# IntegratedSensor.net
KiCad netlist of a schematic drawn in EAGLE
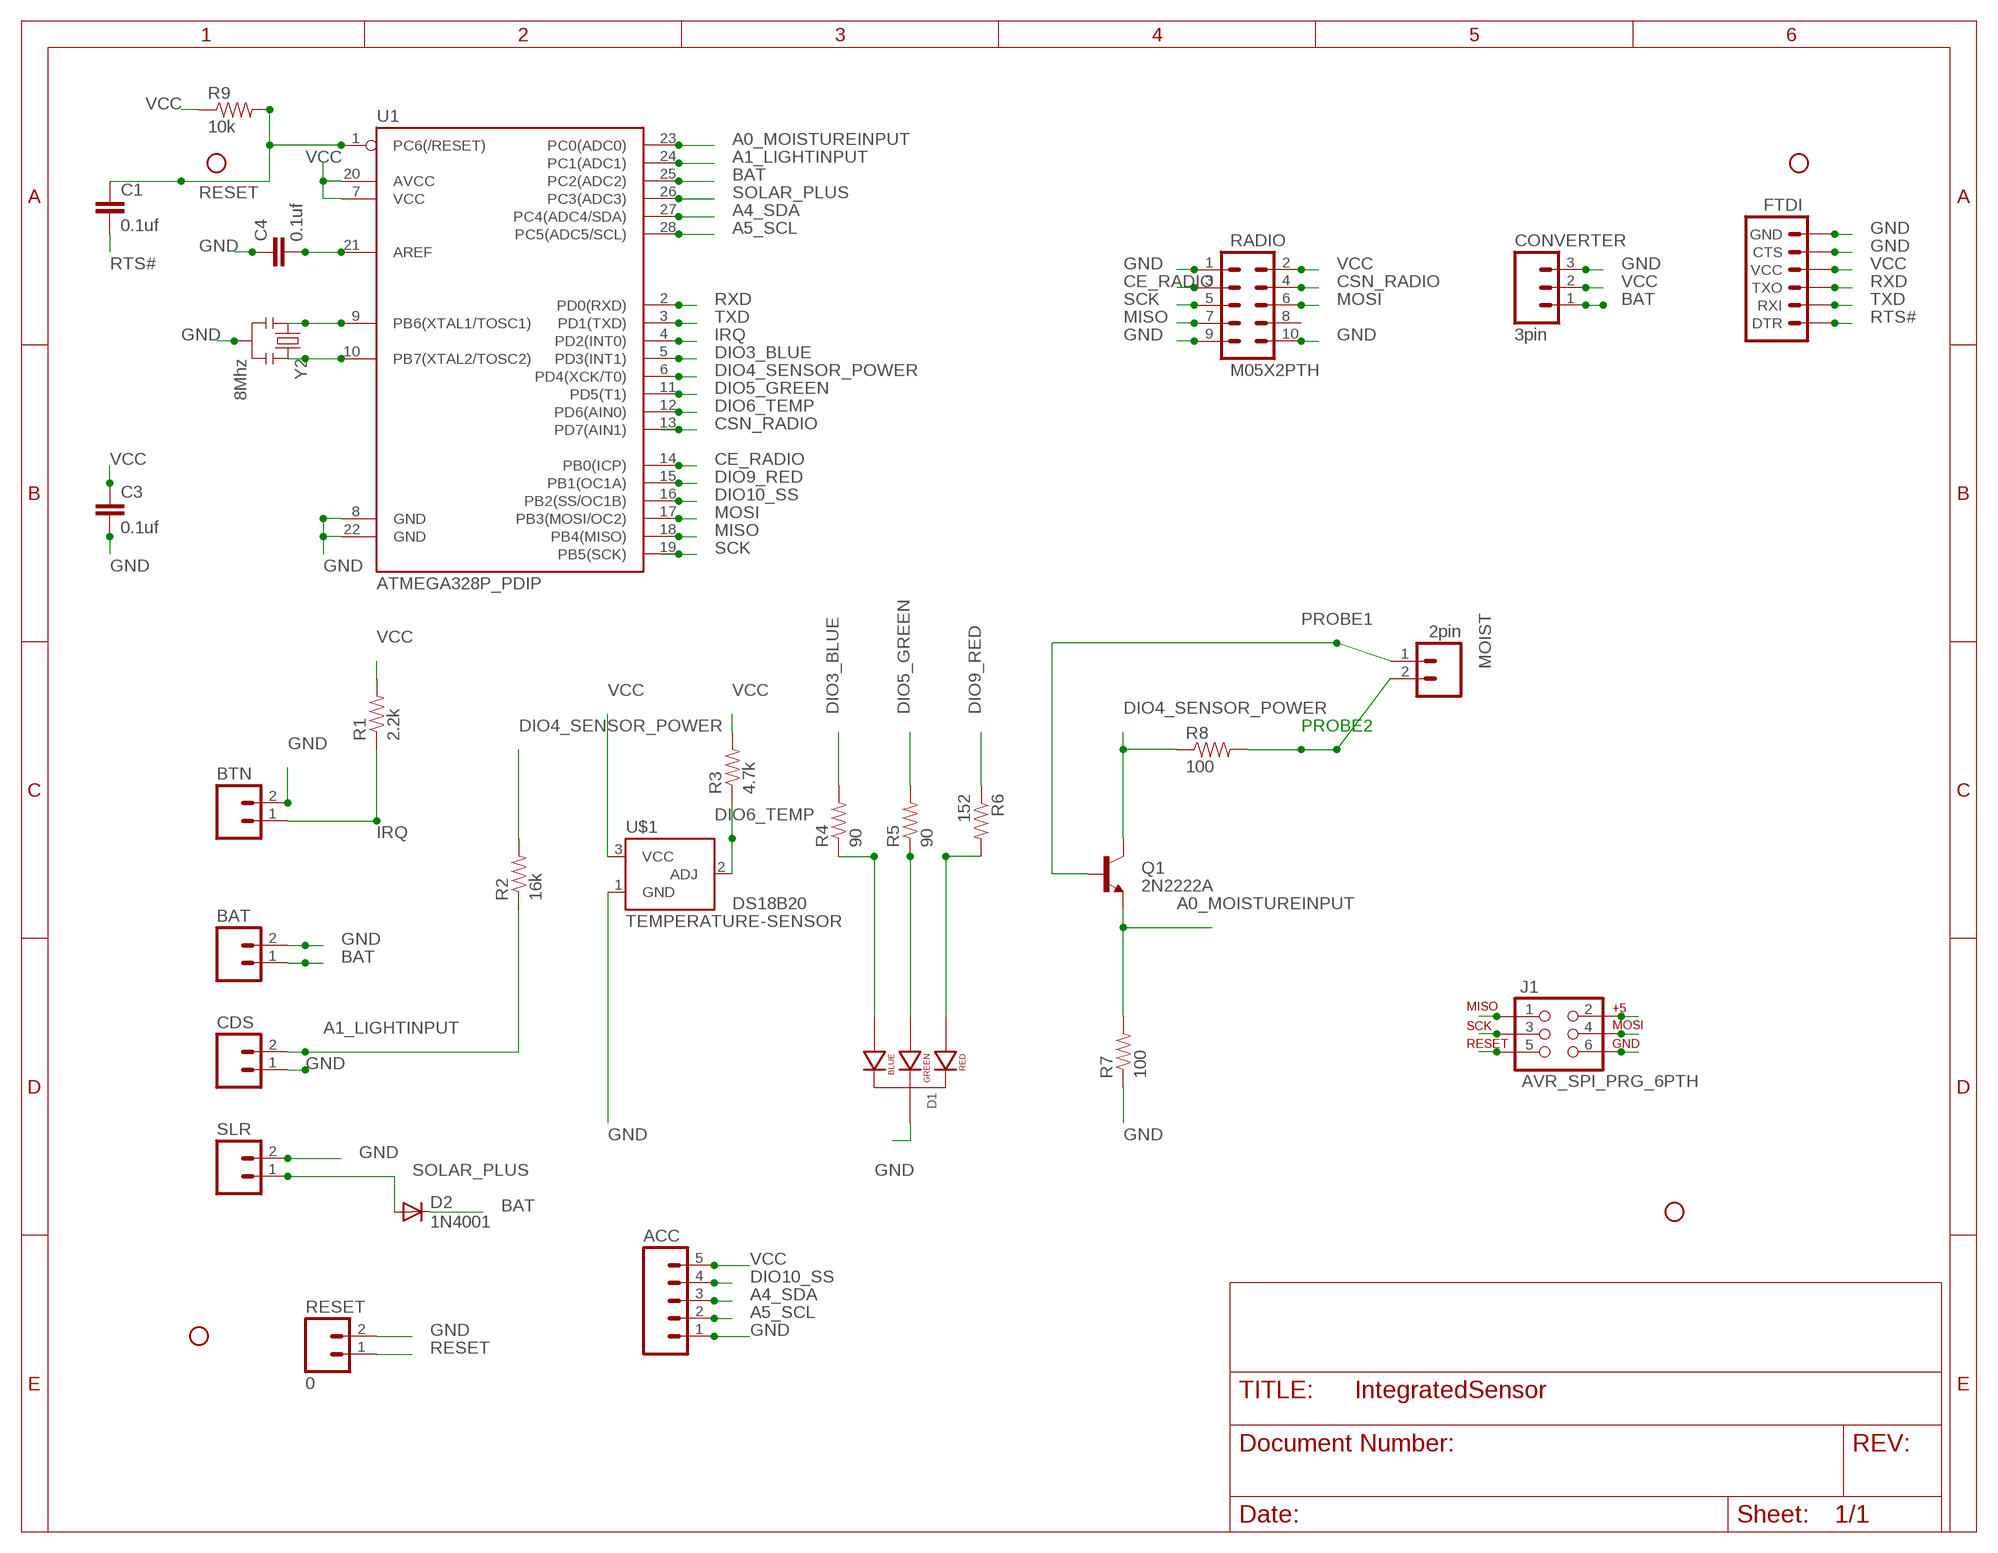
[diagram p0: schematic, sheet 1]

(export (version "E")
  (design (tool "Eeschema 10.0.6"))
  (components
    (comp (ref "ACC")
      (value "M05PTH")
      (footprint "eagle-import:1X05")
      (libsource (lib "eagle-import") (part "M05PTH"))
    )
    (comp (ref "BAT")
      (value "M02PTH")
      (footprint "eagle-import:1X02")
      (libsource (lib "eagle-import") (part "M02PTH"))
    )
    (comp (ref "BTN")
      (value "M02PTH")
      (footprint "eagle-import:1X02")
      (libsource (lib "eagle-import") (part "M02PTH"))
    )
    (comp (ref "C1")
      (value "0.1uf")
      (footprint "eagle-import:CAP-PTH-SMALL")
      (libsource (lib "eagle-import") (part "CAPPTH"))
    )
    (comp (ref "C3")
      (value "0.1uf")
      (footprint "eagle-import:CAP-PTH-SMALL")
      (libsource (lib "eagle-import") (part "CAPPTH"))
    )
    (comp (ref "C4")
      (value "0.1uf")
      (footprint "eagle-import:CAP-PTH-SMALL")
      (libsource (lib "eagle-import") (part "CAPPTH"))
    )
    (comp (ref "CDS")
      (value "M02PTH")
      (footprint "eagle-import:1X02")
      (libsource (lib "eagle-import") (part "M02PTH"))
    )
    (comp (ref "CONVERTER")
      (value "3pin")
      (footprint "eagle-import:1X03")
      (libsource (lib "eagle-import") (part "M03PTH"))
    )
    (comp (ref "D1")
      (value "LED-RGB-CC-THRUCLEAR")
      (footprint "eagle-import:LED-RGB-THRU")
      (libsource (lib "eagle-import") (part "LED-RGB-CC-THRUCLEAR"))
    )
    (comp (ref "D2")
      (value "1N4001")
      (footprint "eagle-import:DIODE-1N4001")
      (libsource (lib "eagle-import") (part "DIODEPTH"))
    )
    (comp (ref "FTDI")
      (value "ARDUINO_SERIAL_PROGRAMPTH")
      (footprint "eagle-import:1X06")
      (libsource (lib "eagle-import") (part "ARDUINO_SERIAL_PROGRAMPTH"))
    )
    (comp (ref "J1")
      (value "AVR_SPI_PRG_6PTH")
      (footprint "eagle-import:2X3")
      (libsource (lib "eagle-import") (part "AVR_SPI_PRG_6PTH"))
    )
    (comp (ref "MOIST")
      (value "2pin")
      (footprint "eagle-import:1X02")
      (libsource (lib "eagle-import") (part "M02PTH"))
    )
    (comp (ref "Q1")
      (value "2N2222A")
      (footprint "eagle-import:TO-92-AMMO")
      (libsource (lib "eagle-import") (part "TRANSISTOR_NPNTO-92-AMMO"))
    )
    (comp (ref "R1")
      (value "2.2k")
      (footprint "eagle-import:1_6W-RES")
      (libsource (lib "eagle-import") (part "RESISTORPTH-1/6W"))
    )
    (comp (ref "R2")
      (value "16k")
      (footprint "eagle-import:1_6W-RES")
      (libsource (lib "eagle-import") (part "RESISTORPTH-1/6W"))
    )
    (comp (ref "R3")
      (value "4.7k")
      (footprint "eagle-import:1_6W-RES")
      (libsource (lib "eagle-import") (part "RESISTORPTH-1/6W"))
    )
    (comp (ref "R4")
      (value "90")
      (footprint "eagle-import:1_6W-RES")
      (libsource (lib "eagle-import") (part "RESISTORPTH-1/6W"))
    )
    (comp (ref "R5")
      (value "90")
      (footprint "eagle-import:1_6W-RES")
      (libsource (lib "eagle-import") (part "RESISTORPTH-1/6W"))
    )
    (comp (ref "R6")
      (value "152")
      (footprint "eagle-import:1_6W-RES")
      (libsource (lib "eagle-import") (part "RESISTORPTH-1/6W"))
    )
    (comp (ref "R7")
      (value "100")
      (footprint "eagle-import:1_6W-RES")
      (libsource (lib "eagle-import") (part "RESISTORPTH-1/6W"))
    )
    (comp (ref "R8")
      (value "100")
      (footprint "eagle-import:1_6W-RES")
      (libsource (lib "eagle-import") (part "RESISTORPTH-1/6W"))
    )
    (comp (ref "R9")
      (value "10k")
      (footprint "eagle-import:1_6W-RES")
      (libsource (lib "eagle-import") (part "RESISTORPTH-1/6W"))
    )
    (comp (ref "RADIO")
      (value "M05X2PTH")
      (footprint "eagle-import:AVR_ICSP")
      (libsource (lib "eagle-import") (part "M05X2PTH"))
    )
    (comp (ref "RESET")
      (value "0")
      (footprint "eagle-import:1X02")
      (libsource (lib "eagle-import") (part "M02PTH"))
    )
    (comp (ref "SLR")
      (value "M02PTH")
      (footprint "eagle-import:1X02")
      (libsource (lib "eagle-import") (part "M02PTH"))
    )
    (comp (ref "STANDOFF1")
      (value "STAND-OFF")
      (footprint "eagle-import:STAND-OFF")
      (libsource (lib "eagle-import") (part "STAND-OFF"))
    )
    (comp (ref "STANDOFF2")
      (value "STAND-OFF")
      (footprint "eagle-import:STAND-OFF")
      (libsource (lib "eagle-import") (part "STAND-OFF"))
    )
    (comp (ref "STANDOFF3")
      (value "STAND-OFF")
      (footprint "eagle-import:STAND-OFF")
      (libsource (lib "eagle-import") (part "STAND-OFF"))
    )
    (comp (ref "STANDOFF4")
      (value "STAND-OFF")
      (footprint "eagle-import:STAND-OFF")
      (libsource (lib "eagle-import") (part "STAND-OFF"))
    )
    (comp (ref "U$1")
      (value "TEMPERATURE-SENSOR")
      (footprint "eagle-import:TO-92")
      (fields (field (name "PARTNAME") "DS18B20"))
      (libsource (lib "eagle-import") (part "TEMPERATURE-SENSOR"))
    )
    (comp (ref "U1")
      (value "ATMEGA328P_PDIP")
      (footprint "eagle-import:DIL28-3")
      (libsource (lib "eagle-import") (part "ATMEGA328P_PDIP"))
    )
    (comp (ref "Y2")
      (value "8Mhz")
      (footprint "eagle-import:RESONATOR-PTH")
      (libsource (lib "eagle-import") (part "RESONATORPTH"))
    )
  )
  (nets
    (net (code "1") (name "/A0_MOISTUREINPUT") (class "Default")
      (node (ref "Q1") (pin "1") (pinfunction "E_1") (pintype "passive"))
      (node (ref "R7") (pin "2") (pinfunction "2_2") (pintype "passive"))
      (node (ref "U1") (pin "23") (pinfunction "PC0(ADC0)_23") (pintype "bidirectional"))
    )
    (net (code "2") (name "/A1_LIGHTINPUT") (class "Default")
      (node (ref "CDS") (pin "2") (pinfunction "2_2") (pintype "passive"))
      (node (ref "R2") (pin "1") (pinfunction "1_1") (pintype "passive"))
      (node (ref "U1") (pin "24") (pinfunction "PC1(ADC1)_24") (pintype "bidirectional"))
    )
    (net (code "3") (name "/A4_SDA") (class "Default")
      (node (ref "ACC") (pin "3") (pinfunction "3_3") (pintype "passive"))
      (node (ref "U1") (pin "27") (pinfunction "PC4(ADC4/SDA)_27") (pintype "bidirectional"))
    )
    (net (code "4") (name "/A5_SCL") (class "Default")
      (node (ref "ACC") (pin "2") (pinfunction "2_2") (pintype "passive"))
      (node (ref "U1") (pin "28") (pinfunction "PC5(ADC5/SCL)_28") (pintype "bidirectional"))
    )
    (net (code "5") (name "/BAT") (class "Default")
      (node (ref "BAT") (pin "1") (pinfunction "1_1") (pintype "passive"))
      (node (ref "CONVERTER") (pin "1") (pinfunction "1_1") (pintype "passive"))
      (node (ref "D2") (pin "C") (pinfunction "C_C") (pintype "passive"))
      (node (ref "U1") (pin "25") (pinfunction "PC2(ADC2)_25") (pintype "bidirectional"))
    )
    (net (code "6") (name "/CE_RADIO") (class "Default")
      (node (ref "RADIO") (pin "3") (pinfunction "3_3") (pintype "passive"))
      (node (ref "U1") (pin "14") (pinfunction "PB0(ICP)_14") (pintype "bidirectional"))
    )
    (net (code "7") (name "/CSN_RADIO") (class "Default")
      (node (ref "RADIO") (pin "4") (pinfunction "4_4") (pintype "passive"))
      (node (ref "U1") (pin "13") (pinfunction "PD7(AIN1)_13") (pintype "bidirectional"))
    )
    (net (code "8") (name "/DIO3_BLUE") (class "Default")
      (node (ref "R4") (pin "2") (pinfunction "2_2") (pintype "passive"))
      (node (ref "U1") (pin "5") (pinfunction "PD3(INT1)_5") (pintype "bidirectional"))
    )
    (net (code "9") (name "/DIO4_SENSOR_POWER") (class "Default")
      (node (ref "Q1") (pin "3") (pinfunction "C_3") (pintype "passive"))
      (node (ref "R2") (pin "2") (pinfunction "2_2") (pintype "passive"))
      (node (ref "R8") (pin "1") (pinfunction "1_1") (pintype "passive"))
      (node (ref "U1") (pin "6") (pinfunction "PD4(XCK/T0)_6") (pintype "bidirectional"))
    )
    (net (code "10") (name "/DIO5_GREEN") (class "Default")
      (node (ref "R5") (pin "2") (pinfunction "2_2") (pintype "passive"))
      (node (ref "U1") (pin "11") (pinfunction "PD5(T1)_11") (pintype "bidirectional"))
    )
    (net (code "11") (name "/DIO6_TEMP") (class "Default")
      (node (ref "R3") (pin "1") (pinfunction "1_1") (pintype "passive"))
      (node (ref "U$1") (pin "2") (pinfunction "ADJ_2") (pintype "bidirectional"))
      (node (ref "U1") (pin "12") (pinfunction "PD6(AIN0)_12") (pintype "bidirectional"))
    )
    (net (code "12") (name "/DIO9_RED") (class "Default")
      (node (ref "R6") (pin "1") (pinfunction "1_1") (pintype "passive"))
      (node (ref "U1") (pin "15") (pinfunction "PB1(OC1A)_15") (pintype "bidirectional"))
    )
    (net (code "13") (name "/DIO10_SS") (class "Default")
      (node (ref "ACC") (pin "4") (pinfunction "4_4") (pintype "passive"))
      (node (ref "U1") (pin "16") (pinfunction "PB2(SS/OC1B)_16") (pintype "bidirectional"))
    )
    (net (code "14") (name "/GND") (class "Default")
      (node (ref "ACC") (pin "1") (pinfunction "1_1") (pintype "passive"))
      (node (ref "BAT") (pin "2") (pinfunction "2_2") (pintype "passive"))
      (node (ref "BTN") (pin "2") (pinfunction "2_2") (pintype "passive"))
      (node (ref "C3") (pin "2") (pinfunction "2_2") (pintype "passive"))
      (node (ref "C4") (pin "1") (pinfunction "1_1") (pintype "passive"))
      (node (ref "CDS") (pin "1") (pinfunction "1_1") (pintype "passive"))
      (node (ref "CONVERTER") (pin "3") (pinfunction "3_3") (pintype "passive"))
      (node (ref "D1") (pin "2") (pinfunction "CATHODE_2") (pintype "bidirectional"))
      (node (ref "FTDI") (pin "5") (pinfunction "CTS_5") (pintype "passive"))
      (node (ref "FTDI") (pin "6") (pinfunction "GND_6") (pintype "passive"))
      (node (ref "J1") (pin "6") (pinfunction "6_6") (pintype "passive"))
      (node (ref "R7") (pin "1") (pinfunction "1_1") (pintype "passive"))
      (node (ref "RADIO") (pin "1") (pinfunction "1_1") (pintype "passive"))
      (node (ref "RADIO") (pin "10") (pinfunction "10_10") (pintype "passive"))
      (node (ref "RADIO") (pin "9") (pinfunction "9_9") (pintype "passive"))
      (node (ref "RESET") (pin "2") (pinfunction "2_2") (pintype "passive"))
      (node (ref "SLR") (pin "2") (pinfunction "2_2") (pintype "passive"))
      (node (ref "U$1") (pin "1") (pinfunction "GND_1") (pintype "bidirectional"))
      (node (ref "U1") (pin "22") (pinfunction "GND_22") (pintype "bidirectional"))
      (node (ref "U1") (pin "8") (pinfunction "GND_8") (pintype "bidirectional"))
      (node (ref "Y2") (pin "2") (pinfunction "2_2") (pintype "passive"))
    )
    (net (code "15") (name "/IRQ") (class "Default")
      (node (ref "BTN") (pin "1") (pinfunction "1_1") (pintype "passive"))
      (node (ref "R1") (pin "1") (pinfunction "1_1") (pintype "passive"))
      (node (ref "U1") (pin "4") (pinfunction "PD2(INT0)_4") (pintype "bidirectional"))
    )
    (net (code "16") (name "/MISO") (class "Default")
      (node (ref "J1") (pin "1") (pinfunction "1_1") (pintype "passive"))
      (node (ref "RADIO") (pin "7") (pinfunction "7_7") (pintype "passive"))
      (node (ref "U1") (pin "18") (pinfunction "PB4(MISO)_18") (pintype "bidirectional"))
    )
    (net (code "17") (name "/MOSI") (class "Default")
      (node (ref "J1") (pin "4") (pinfunction "4_4") (pintype "passive"))
      (node (ref "RADIO") (pin "6") (pinfunction "6_6") (pintype "passive"))
      (node (ref "U1") (pin "17") (pinfunction "PB3(MOSI/OC2)_17") (pintype "bidirectional"))
    )
    (net (code "18") (name "/PROBE1") (class "Default")
      (node (ref "MOIST") (pin "1") (pinfunction "1_1") (pintype "passive"))
      (node (ref "Q1") (pin "2") (pinfunction "B_2") (pintype "passive"))
    )
    (net (code "19") (name "/PROBE2") (class "Default")
      (node (ref "MOIST") (pin "2") (pinfunction "2_2") (pintype "passive"))
      (node (ref "R8") (pin "2") (pinfunction "2_2") (pintype "passive"))
    )
    (net (code "20") (name "/RESET") (class "Default")
      (node (ref "C1") (pin "1") (pinfunction "1_1") (pintype "passive"))
      (node (ref "J1") (pin "5") (pinfunction "5_5") (pintype "passive"))
      (node (ref "R9") (pin "2") (pinfunction "2_2") (pintype "passive"))
      (node (ref "RESET") (pin "1") (pinfunction "1_1") (pintype "passive"))
      (node (ref "U1") (pin "1") (pinfunction "PC6(/RESET)_1") (pintype "bidirectional"))
    )
    (net (code "21") (name "/RTS#") (class "Default")
      (node (ref "C1") (pin "2") (pinfunction "2_2") (pintype "passive"))
      (node (ref "FTDI") (pin "1") (pinfunction "DTR_1") (pintype "passive"))
    )
    (net (code "22") (name "/RXD") (class "Default")
      (node (ref "FTDI") (pin "3") (pinfunction "TXO_3") (pintype "passive"))
      (node (ref "U1") (pin "2") (pinfunction "PD0(RXD)_2") (pintype "bidirectional"))
    )
    (net (code "23") (name "/SCK") (class "Default")
      (node (ref "J1") (pin "3") (pinfunction "3_3") (pintype "passive"))
      (node (ref "RADIO") (pin "5") (pinfunction "5_5") (pintype "passive"))
      (node (ref "U1") (pin "19") (pinfunction "PB5(SCK)_19") (pintype "bidirectional"))
    )
    (net (code "24") (name "/SOLAR_PLUS") (class "Default")
      (node (ref "D2") (pin "A") (pinfunction "A_A") (pintype "passive"))
      (node (ref "SLR") (pin "1") (pinfunction "1_1") (pintype "passive"))
      (node (ref "U1") (pin "26") (pinfunction "PC3(ADC3)_26") (pintype "bidirectional"))
    )
    (net (code "25") (name "/TXD") (class "Default")
      (node (ref "FTDI") (pin "2") (pinfunction "RXI_2") (pintype "passive"))
      (node (ref "U1") (pin "3") (pinfunction "PD1(TXD)_3") (pintype "bidirectional"))
    )
    (net (code "26") (name "/VCC") (class "Default")
      (node (ref "ACC") (pin "5") (pinfunction "5_5") (pintype "passive"))
      (node (ref "C3") (pin "1") (pinfunction "1_1") (pintype "passive"))
      (node (ref "CONVERTER") (pin "2") (pinfunction "2_2") (pintype "passive"))
      (node (ref "FTDI") (pin "4") (pinfunction "VCC_4") (pintype "passive"))
      (node (ref "J1") (pin "2") (pinfunction "2_2") (pintype "passive"))
      (node (ref "R1") (pin "2") (pinfunction "2_2") (pintype "passive"))
      (node (ref "R3") (pin "2") (pinfunction "2_2") (pintype "passive"))
      (node (ref "R9") (pin "1") (pinfunction "1_1") (pintype "passive"))
      (node (ref "RADIO") (pin "2") (pinfunction "2_2") (pintype "passive"))
      (node (ref "U$1") (pin "3") (pinfunction "VCC_3") (pintype "bidirectional"))
      (node (ref "U1") (pin "20") (pinfunction "AVCC_20") (pintype "bidirectional"))
      (node (ref "U1") (pin "7") (pinfunction "VCC_7") (pintype "bidirectional"))
    )
    (net (code "27") (name "Net-(D1-BLUE_CATHODE)") (class "Default")
      (node (ref "D1") (pin "4") (pinfunction "BLUE_CATHODE_4") (pintype "bidirectional"))
      (node (ref "R4") (pin "1") (pinfunction "1_1") (pintype "passive"))
    )
    (net (code "28") (name "Net-(D1-GREEN_CATHODE)") (class "Default")
      (node (ref "D1") (pin "3") (pinfunction "GREEN_CATHODE_3") (pintype "bidirectional"))
      (node (ref "R5") (pin "1") (pinfunction "1_1") (pintype "passive"))
    )
    (net (code "29") (name "Net-(D1-RED_CATHODE)") (class "Default")
      (node (ref "D1") (pin "1") (pinfunction "RED_CATHODE_1") (pintype "bidirectional"))
      (node (ref "R6") (pin "2") (pinfunction "2_2") (pintype "passive"))
    )
    (net (code "30") (name "Net-(U1-AREF)") (class "Default")
      (node (ref "C4") (pin "2") (pinfunction "2_2") (pintype "passive"))
      (node (ref "U1") (pin "21") (pinfunction "AREF_21") (pintype "bidirectional"))
    )
    (net (code "31") (name "Net-(U1-PB6(XTAL1{slash}TOSC1))") (class "Default")
      (node (ref "U1") (pin "9") (pinfunction "PB6(XTAL1/TOSC1)_9") (pintype "bidirectional"))
      (node (ref "Y2") (pin "1") (pinfunction "1_1") (pintype "passive"))
    )
    (net (code "32") (name "Net-(U1-PB7(XTAL2{slash}TOSC2))") (class "Default")
      (node (ref "U1") (pin "10") (pinfunction "PB7(XTAL2/TOSC2)_10") (pintype "bidirectional"))
      (node (ref "Y2") (pin "3") (pinfunction "3_3") (pintype "passive"))
    )
    (net (code "33") (name "unconnected-(RADIO-Pad8)") (class "Default")
      (node (ref "RADIO") (pin "8") (pinfunction "8_8") (pintype "passive"))
    )
  )
)
